# Power_Management.net
KiCad netlist of a schematic drawn in Altium Designer
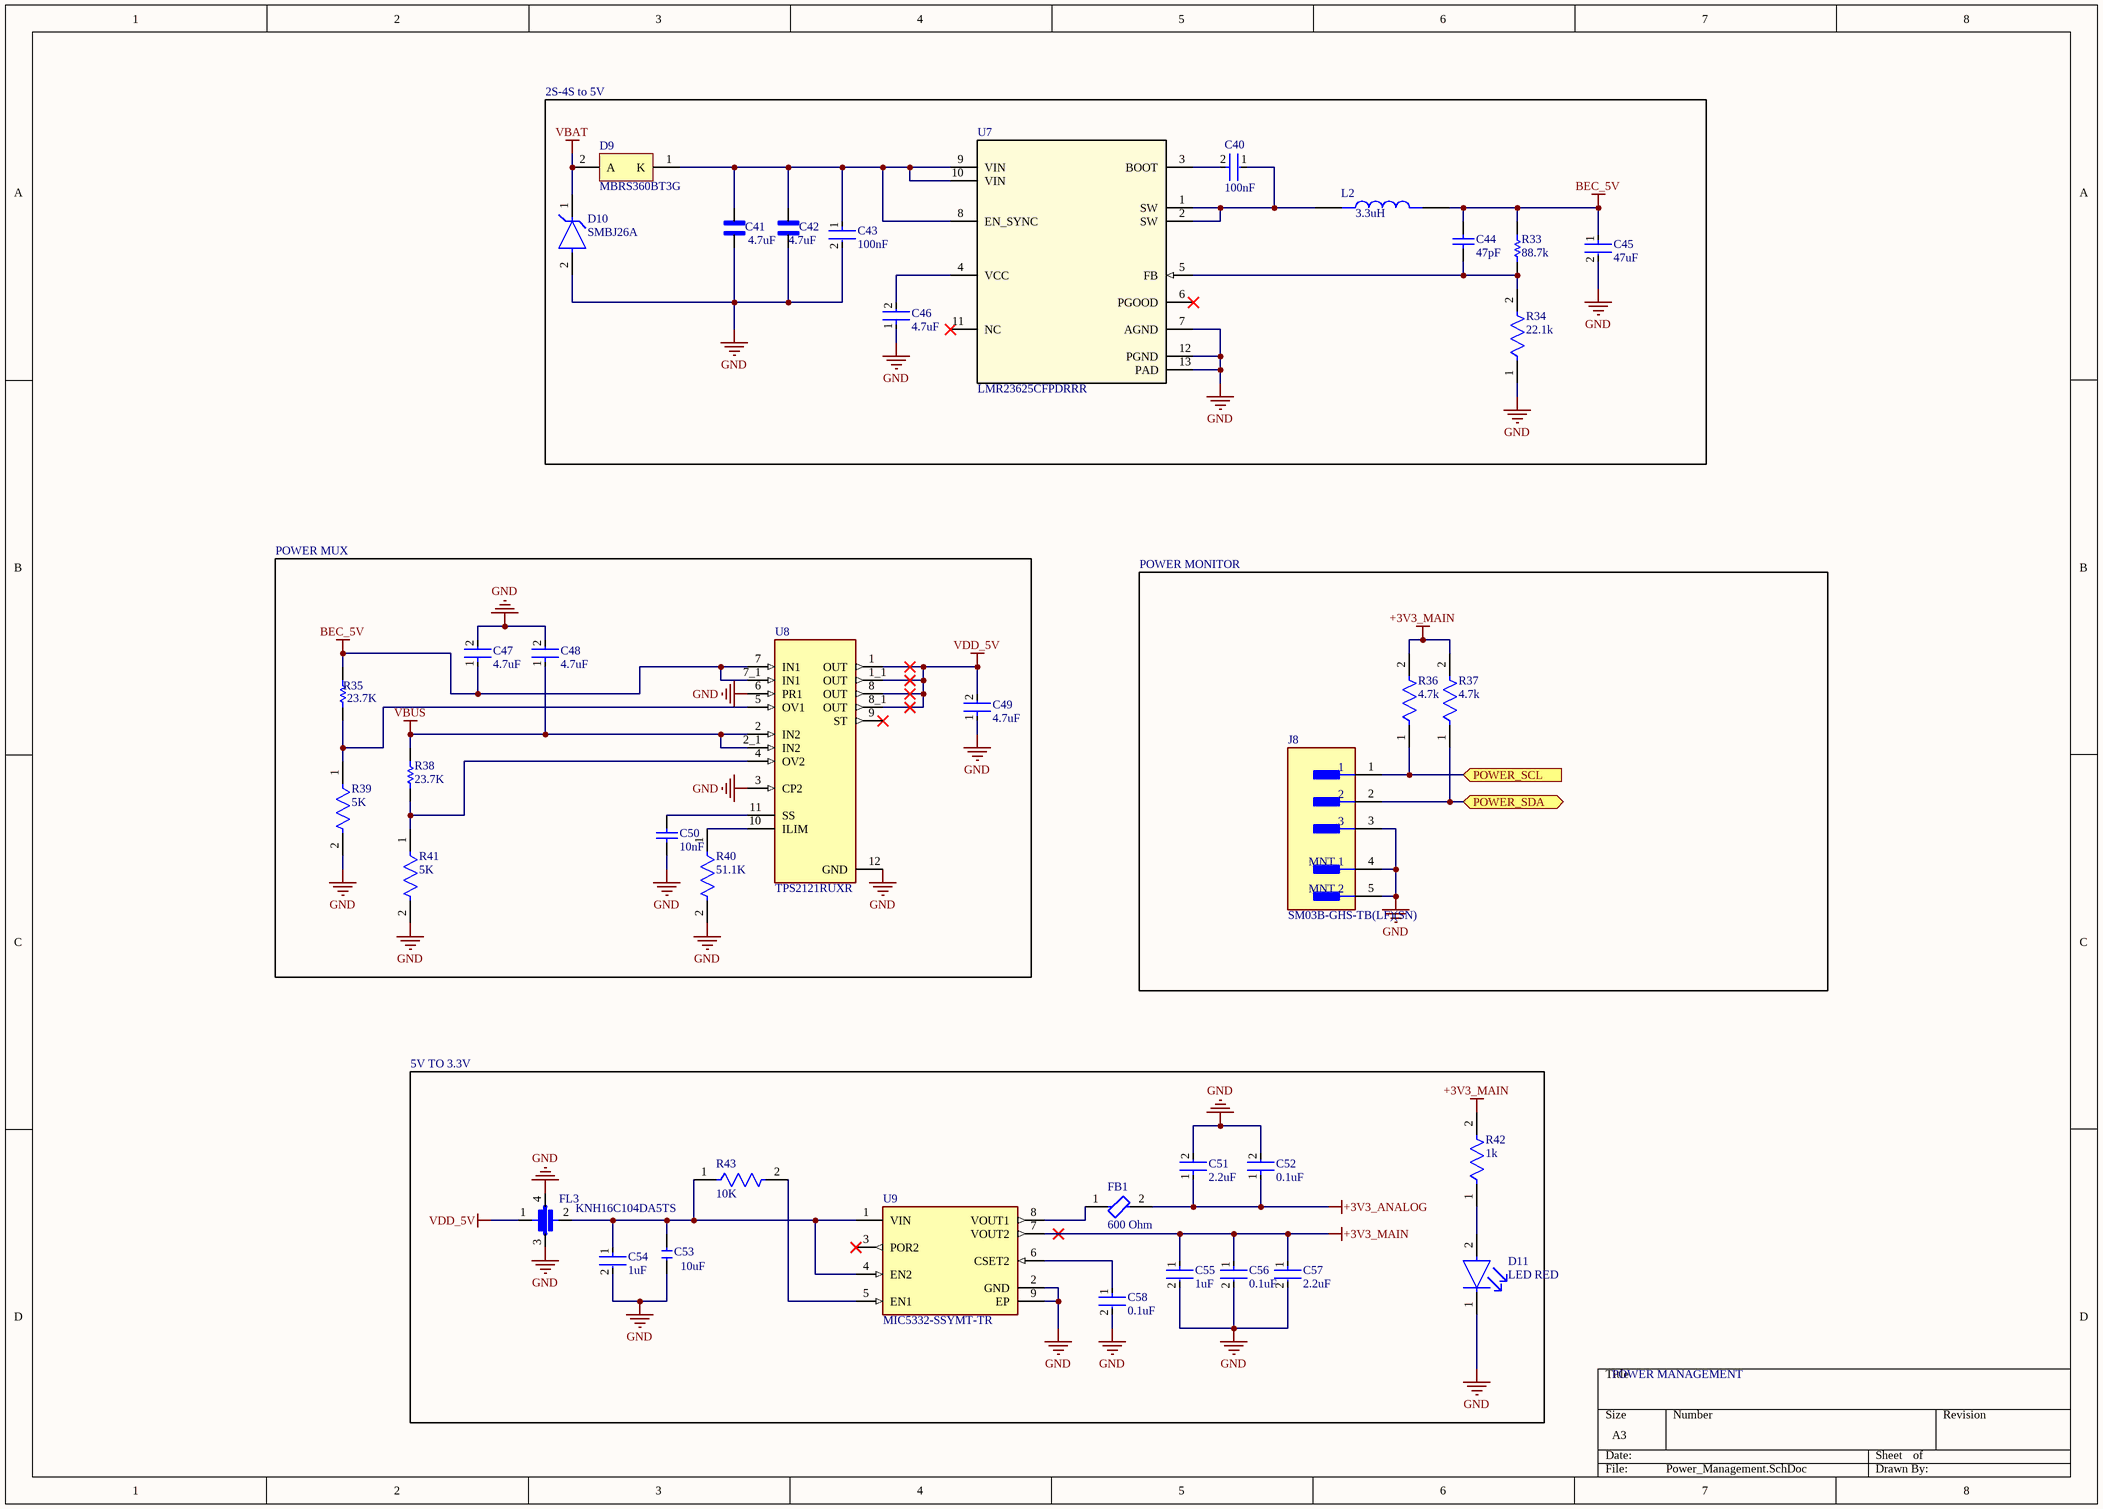
[diagram p0: Power_Management.SchDoc]

(export (version "E")
  (design (tool "Eeschema 10.0.6"))
  (components
    (comp (ref "C40")
      (value "100nF")
      (footprint "FP-GRM15-MFG")
      (description "CAP CER 0.1UF 16V X7R 0402")
      (fields (field (name "MANUFACTURER PART NUMBER") "GRM155R71C104KA88D") (field (name "TOLERANCE") "10%"))
      (libsource (lib "Altium Content Vault") (part "236180d848d6139a670b325ea6854c9"))
    )
    (comp (ref "C41")
      (value "MSASU32MSB7475MPNA01")
      (footprint "CAPC3225X270N")
      (fields (field (name "MF") "{'manufacturer': u'Taiyo Yuden'}"))
      (libsource (lib "4.7uF CAP") (part "MSASU32MSB7475MPNA01"))
    )
    (comp (ref "C42")
      (value "MSASU32MSB7475MPNA01")
      (footprint "CAPC3225X270N")
      (fields (field (name "MF") "{'manufacturer': u'Taiyo Yuden'}"))
      (libsource (lib "4.7uF CAP") (part "MSASU32MSB7475MPNA01"))
    )
    (comp (ref "C43")
      (value "100nF")
      (footprint "FP-CS0402-CA-MFG")
      (description "CS0402KRX7R8BB104 Multilayer Ceramic Capacitor, 0.1 uF, 25 V, ± 10%, X7R, 0402 [1005 Metric]")
      (fields (field (name "TOLERANCE") "10%"))
      (libsource (lib "Altium Content Vault") (part "11868f565c42a9108669ba33697ecf6"))
    )
    (comp (ref "C44")
      (value "47pF")
      (footprint "CAPC1005X55X25NL05T10")
      (fields (field (name "PART NUMBER") "GRM1555C1E470JA01D") (field (name "MANUFACTURER") "Murata"))
      (libsource (lib "Altium Content Vault") (part "CAP"))
    )
    (comp (ref "C45")
      (value "47uF")
      (footprint "FP-GRM31C-0_2-e0_3_0_8-IPC_A")
      (description "Chip Multilayer Ceramic Capacitors for General Purpose, 1206, 47uF, X5R, 15%, 10%, 10V")
      (fields (field (name "TOLERANCE") "10%"))
      (libsource (lib "Altium Content Vault") (part "02cd4be3c70576c341d710602a673aa"))
    )
    (comp (ref "C46")
      (value "4.7uF")
      (footprint "FP-GRT155-0_15-MFG")
      (description "Multi-Layer Ceramic Capacitor 4.7uF 10V X5R ±20% 0402 Paper T/R")
      (libsource (lib "Altium Content Vault") (part "11868f565c42a9108669ba33697ecf6"))
    )
    (comp (ref "C47")
      (value "4.7uF")
      (footprint "FP-GRT155-0_15-MFG")
      (description "Multi-Layer Ceramic Capacitor 4.7uF 10V X5R ±20% 0402 Paper T/R")
      (libsource (lib "Altium Content Vault") (part "11868f565c42a9108669ba33697ecf6"))
    )
    (comp (ref "C48")
      (value "4.7uF")
      (footprint "FP-GRT155-0_15-MFG")
      (description "Multi-Layer Ceramic Capacitor 4.7uF 10V X5R ±20% 0402 Paper T/R")
      (libsource (lib "Altium Content Vault") (part "11868f565c42a9108669ba33697ecf6"))
    )
    (comp (ref "C49")
      (value "4.7uF")
      (footprint "FP-GRT155-0_15-MFG")
      (description "Multi-Layer Ceramic Capacitor 4.7uF 10V X5R ±20% 0402 Paper T/R")
      (libsource (lib "Altium Content Vault") (part "11868f565c42a9108669ba33697ecf6"))
    )
    (comp (ref "C50")
      (value "10nF")
      (footprint "CAPC1005X60X30NL05T10")
      (fields (field (name "PART NUMBER") "C0402C103K3RALTU") (field (name "MANUFACTURER") "Kemet"))
      (libsource (lib "Altium Content Vault") (part "CAP"))
    )
    (comp (ref "C51")
      (value "2.2uF")
      (footprint "FP-GRM155-0_2-IPC_B")
      (description "Chip Multilayer Ceramic Capacitors for General Purpose, 0402, 2.2uF, X7R, 15%, 10%, 10V")
      (libsource (lib "Altium Content Vault") (part "b4654b650e69147ec39a6b967a45e02"))
    )
    (comp (ref "C52")
      (value "0.1uF")
      (footprint "FP-C0402-BB-MFG")
      (description "CAP CER 0.1UF 10V X7R 0402")
      (fields (field (name "MANUFACTURER") "Kemet") (field (name "TOLERANCE") "0.1"))
      (libsource (lib "Altium Content Vault") (part "b4654b650e69147ec39a6b967a45e02"))
    )
    (comp (ref "C53")
      (value "GRM155R60J106ME15D")
      (footprint "C0402")
      (description "10 ÂµF Â±20% 6.3V Ceramic Capacitor X5R 0402 (1005 Metric)")
      (fields (field (name "MF") "Yageo") (field (name "MP") "CC0402MRX5R5BB106"))
      (libsource (lib "CERAMIC-10UF-6.3V-20_-X5R_0402_") (part "CERAMIC-10UF-6.3V-20%-X5R(0402)"))
    )
    (comp (ref "C54")
      (value "1uF")
      (footprint "FP-GRM155-0_1-IPC_A")
      (description "Chip Multilayer Ceramic Capacitors for General Purpose, 0402, 1.0uF, X7R, 15%, 10%, 10V")
      (libsource (lib "Altium Content Vault") (part "11868f565c42a9108669ba33697ecf6"))
    )
    (comp (ref "C55")
      (value "1uF")
      (footprint "FP-GRM155-0_1-IPC_A")
      (description "Chip Multilayer Ceramic Capacitors for General Purpose, 0402, 1.0uF, X7R, 15%, 10%, 10V")
      (libsource (lib "Altium Content Vault") (part "11868f565c42a9108669ba33697ecf6"))
    )
    (comp (ref "C56")
      (value "0.1uF")
      (footprint "FP-C0402-BB-MFG")
      (description "CAP CER 0.1UF 10V X7R 0402")
      (fields (field (name "MANUFACTURER") "Kemet") (field (name "TOLERANCE") "0.1"))
      (libsource (lib "Altium Content Vault") (part "b4654b650e69147ec39a6b967a45e02"))
    )
    (comp (ref "C57")
      (value "2.2uF")
      (footprint "FP-GRM155-0_2-IPC_B")
      (description "Chip Multilayer Ceramic Capacitors for General Purpose, 0402, 2.2uF, X7R, 15%, 10%, 10V")
      (libsource (lib "Altium Content Vault") (part "b4654b650e69147ec39a6b967a45e02"))
    )
    (comp (ref "C58")
      (value "0.1uF")
      (footprint "FP-C0402-BB-MFG")
      (description "CAP CER 0.1UF 10V X7R 0402")
      (fields (field (name "MANUFACTURER") "Kemet") (field (name "TOLERANCE") "0.1"))
      (libsource (lib "Altium Content Vault") (part "b4654b650e69147ec39a6b967a45e02"))
    )
    (comp (ref "D9")
      (value "MBRS360BT3G")
      (footprint "ONSC-SMB-2-403A-03_H_V")
      (description "Schottky Power Rectifier, 2-Pin SMB, Pb-Free, Tape and Reel")
      (fields (field (name "MANUFACTURER") "On Semiconductor"))
      (libsource (lib "Altium Content Vault") (part "ONSC-D-K1A2-2_A"))
    )
    (comp (ref "D10")
      (value "SMBJ26A")
      (footprint "FP-SMBJ-MFG")
      (description "TVS DIODE 26V 42.1V DO214AA")
      (fields
        (field (name "MANUFACTURER") "Littelfuse")
        (field (name "OCTOPART") "https://octopart.com/smbj26a-littelfuse-350771")
      )
      (libsource (lib "Altium Content Vault") (part "f813f71cba58e380607f5dd3caf9714"))
    )
    (comp (ref "D11")
      (value "LED RED")
      (footprint "FP-SML-LXT0805IW-TR-MFG")
      (description "LED RED DIFFUSED SMD")
      (libsource (lib "Altium Content Vault") (part "8706943c75ba83719d021d2fdc84c58"))
    )
    (comp (ref "FB1")
      (value "600 Ohm")
      (footprint "FP-BLM15-0_05-MFG")
      (description "BLM15PE601SH1D Ferrite Bead, 600 Ohm, 25%, 0402 Rohs Compliant: Yes")
      (fields (field (name "TOLERANCE") "25%"))
      (libsource (lib "Altium Content Vault") (part "5f30dd21d616792df468990f7003faa"))
    )
    (comp (ref "FL3")
      (value "KNH16C104DA5TS")
      (footprint "FIL_KNH16C104DA5TS")
      (fields (field (name "MF") "{'manufacturer': u'KYOCERA AVX'}"))
      (libsource (lib "KNH16C104DA5TS") (part "KNH16C104DA5TS"))
    )
    (comp (ref "J8")
      (value "SM03B-GHS-TB(LF)(SN)")
      (footprint "FP-SM03B-GHS-TB_LF_SN-MFG")
      (description "CONN HEADER SMD R/A 3POS 1.25MM")
      (libsource (lib "Altium Content Vault") (part "13850a6865a90496d8e6d51657cef87"))
    )
    (comp (ref "L2")
      (value "IND_XAL4030-332MEB")
      (footprint "IND_XAL4030-332MEB")
      (fields (field (name "MP") "XAL4030-332MEB"))
      (libsource (lib "3.2uH") (part "XAL4030-332MEB"))
    )
    (comp (ref "R33")
      (value "88.7k")
      (footprint "RESC1005X40X25NL05T05")
      (fields (field (name "MANUFACTURER") "Vishay Dale") (field (name "PART NUMBER") "CRCW040288K7FKED"))
      (libsource (lib "Altium Content Vault") (part "RES"))
    )
    (comp (ref "R34")
      (value "22.1k")
      (footprint "FP-CRCW0402-e3-IPC_A")
      (description "RES Thick Film, 22.1kΩ, 1%, 0.063W, 100ppm/°C, 0402")
      (fields (field (name "TOLERANCE") "1%"))
      (libsource (lib "Altium Content Vault") (part "1029c3af85768c4190bb7ad29bc67b5"))
    )
    (comp (ref "R35")
      (value "23.7K")
      (footprint "RESC1005X40X25LL05T05")
      (fields (field (name "MANUFACTURER") "Vishay Dale") (field (name "PART NUMBER") "CRCW040223K7FKTD"))
      (libsource (lib "Altium Content Vault") (part "RES"))
    )
    (comp (ref "R36")
      (value "4.7k")
      (footprint "FP-TFCR0402-IPC_A")
      (description "RES Thin Film,  4.7kΩ, 0.5%, 0.063W, 25ppm/°C, 0402")
      (libsource (lib "Altium Content Vault") (part "1029c3af85768c4190bb7ad29bc67b5"))
    )
    (comp (ref "R37")
      (value "4.7k")
      (footprint "FP-TFCR0402-IPC_A")
      (description "RES Thin Film,  4.7kΩ, 0.5%, 0.063W, 25ppm/°C, 0402")
      (libsource (lib "Altium Content Vault") (part "1029c3af85768c4190bb7ad29bc67b5"))
    )
    (comp (ref "R38")
      (value "23.7K")
      (footprint "RESC1005X40X25LL05T05")
      (fields (field (name "MANUFACTURER") "Vishay Dale") (field (name "PART NUMBER") "CRCW040223K7FKTD"))
      (libsource (lib "Altium Content Vault") (part "RES"))
    )
    (comp (ref "R39")
      (value "5K")
      (footprint "FP-PNM0402-IPC_C")
      (description "RES SMD 5K OHM 0.1% 1/20W 0402")
      (fields (field (name "TOLERANCE") "0.1%"))
      (libsource (lib "Altium Content Vault") (part "1029c3af85768c4190bb7ad29bc67b5"))
    )
    (comp (ref "R40")
      (value "51.1K")
      (footprint "FP-RK73H1E-IPC_C")
      (description "51.1kΩ ±1% 0.1W Chip Resistor 0402 Thick Film AEC-Q200 Qualified")
      (fields (field (name "TOLERANCE") "1%"))
      (libsource (lib "Altium Content Vault") (part "1029c3af85768c4190bb7ad29bc67b5"))
    )
    (comp (ref "R41")
      (value "5K")
      (footprint "FP-PNM0402-IPC_C")
      (description "RES SMD 5K OHM 0.1% 1/20W 0402")
      (fields (field (name "TOLERANCE") "0.1%"))
      (libsource (lib "Altium Content Vault") (part "1029c3af85768c4190bb7ad29bc67b5"))
    )
    (comp (ref "R42")
      (value "1k")
      (footprint "FP-MCS0402-IPC_A")
      (description "RES SMD 1.2K OHM 1% 1/10W 0402")
      (fields (field (name "TOLERANCE") "0.5%"))
      (libsource (lib "Altium Content Vault") (part "1029c3af85768c4190bb7ad29bc67b5"))
    )
    (comp (ref "R43")
      (value "10K")
      (footprint "FP-MCS0402-MFG")
      (description "RES SMD 1.2K OHM 1% 1/10W 0402")
      (fields (field (name "TOLERANCE") "0.5%"))
      (libsource (lib "Altium Content Vault") (part "1029c3af85768c4190bb7ad29bc67b5"))
    )
    (comp (ref "U7")
      (value "LMR23625CFPDRRR")
      (footprint "DRR0012D")
      (description "SIMPLE SWITCHERÂ®, 36V 2.5A Synchronous Step-Down Converter 12-WSON -40 to 125")
      (fields (field (name "COPYRIGHT") "Copyright (C) 2025 Ultra Librarian. All rights reserved."))
      (libsource (lib "LMR23625CFPDRRR") (part "LMR23625CFPDRRR"))
    )
    (comp (ref "U8")
      (value "TPS2121RUXR")
      (footprint "IC_TPS2121RUXR")
      (description "2.7-V&nbsp;to 22-V, 56-mâ„¦, 4.5-A, power mux with seamless switchover")
      (fields (field (name "MF") "Texas Instruments"))
      (libsource (lib "TPS2121RUXR") (part "TPS2121RUXR"))
    )
    (comp (ref "U9")
      (value "MIC5332-SSYMT-TR")
      (footprint "FP-MIC5332-SSYMT-TR-IPC_C")
      (description "IC REG LINEAR 3.3V/3.3V 8TMLF")
      (libsource (lib "Altium Content Vault") (part "3cda86a0174568058fc5e6010d9da67"))
    )
  )
  (nets
    (net (code "1") (name "+3V3_ANALOG") (class "Default")
      (node (ref "C51") (pin "1") (pinfunction "1_1") (pintype "passive"))
      (node (ref "C52") (pin "1") (pinfunction "1_1") (pintype "passive"))
      (node (ref "FB1") (pin "2") (pinfunction "2_2") (pintype "passive"))
    )
    (net (code "2") (name "+3V3_MAIN") (class "Default")
      (node (ref "C55") (pin "1") (pinfunction "1_1") (pintype "passive"))
      (node (ref "C56") (pin "1") (pinfunction "1_1") (pintype "passive"))
      (node (ref "C57") (pin "1") (pinfunction "1_1") (pintype "passive"))
      (node (ref "R36") (pin "2") (pinfunction "2_2") (pintype "passive"))
      (node (ref "R37") (pin "2") (pinfunction "2_2") (pintype "passive"))
      (node (ref "R42") (pin "2") (pinfunction "2_2") (pintype "passive"))
      (node (ref "U9") (pin "7") (pinfunction "VOUT2_7") (pintype "output"))
    )
    (net (code "3") (name "/POWER_SCL") (class "Default")
      (node (ref "J8") (pin "1") (pinfunction "1_1") (pintype "passive"))
      (node (ref "R36") (pin "1") (pinfunction "1_1") (pintype "passive"))
    )
    (net (code "4") (name "/POWER_SDA") (class "Default")
      (node (ref "J8") (pin "2") (pinfunction "2_2") (pintype "passive"))
      (node (ref "R37") (pin "1") (pinfunction "1_1") (pintype "passive"))
    )
    (net (code "5") (name "BEC_5V") (class "Default")
      (node (ref "C44") (pin "2") (pinfunction "2_2") (pintype "passive"))
      (node (ref "C45") (pin "1") (pinfunction "1_1") (pintype "passive"))
      (node (ref "C47") (pin "1") (pinfunction "1_1") (pintype "passive"))
      (node (ref "L2") (pin "2") (pinfunction "2_2") (pintype "passive"))
      (node (ref "R33") (pin "2") (pinfunction "2_2") (pintype "passive"))
      (node (ref "R35") (pin "2") (pinfunction "2_2") (pintype "passive"))
      (node (ref "U8") (pin "7") (pinfunction "IN1_7") (pintype "input"))
      (node (ref "U8") (pin "7_1") (pinfunction "IN1_7_1") (pintype "input"))
    )
    (net (code "6") (name "GND") (class "Default")
      (node (ref "C41") (pin "1") (pinfunction "1_1") (pintype "passive"))
      (node (ref "C42") (pin "1") (pinfunction "1_1") (pintype "passive"))
      (node (ref "C43") (pin "2") (pinfunction "2_2") (pintype "passive"))
      (node (ref "C45") (pin "2") (pinfunction "2_2") (pintype "passive"))
      (node (ref "C46") (pin "1") (pinfunction "1_1") (pintype "passive"))
      (node (ref "C47") (pin "2") (pinfunction "2_2") (pintype "passive"))
      (node (ref "C48") (pin "2") (pinfunction "2_2") (pintype "passive"))
      (node (ref "C49") (pin "1") (pinfunction "1_1") (pintype "passive"))
      (node (ref "C50") (pin "1") (pinfunction "1_1") (pintype "passive"))
      (node (ref "C51") (pin "2") (pinfunction "2_2") (pintype "passive"))
      (node (ref "C52") (pin "2") (pinfunction "2_2") (pintype "passive"))
      (node (ref "C53") (pin "1") (pinfunction "1_1") (pintype "passive"))
      (node (ref "C54") (pin "2") (pinfunction "2_2") (pintype "passive"))
      (node (ref "C55") (pin "2") (pinfunction "2_2") (pintype "passive"))
      (node (ref "C56") (pin "2") (pinfunction "2_2") (pintype "passive"))
      (node (ref "C57") (pin "2") (pinfunction "2_2") (pintype "passive"))
      (node (ref "C58") (pin "2") (pinfunction "2_2") (pintype "passive"))
      (node (ref "D10") (pin "2") (pinfunction "A_2") (pintype "passive"))
      (node (ref "D11") (pin "1") (pinfunction "C_1") (pintype "passive"))
      (node (ref "FL3") (pin "3") (pinfunction "3_3") (pintype "passive"))
      (node (ref "FL3") (pin "4") (pinfunction "4_4") (pintype "passive"))
      (node (ref "J8") (pin "3") (pinfunction "3_3") (pintype "passive"))
      (node (ref "J8") (pin "4") (pinfunction "MNT_1_4") (pintype "passive"))
      (node (ref "J8") (pin "5") (pinfunction "MNT_2_5") (pintype "passive"))
      (node (ref "R34") (pin "1") (pinfunction "1_1") (pintype "passive"))
      (node (ref "R39") (pin "2") (pinfunction "2_2") (pintype "passive"))
      (node (ref "R40") (pin "2") (pinfunction "2_2") (pintype "passive"))
      (node (ref "R41") (pin "2") (pinfunction "2_2") (pintype "passive"))
      (node (ref "U7") (pin "12") (pinfunction "PGND_12") (pintype "power_in"))
      (node (ref "U7") (pin "13") (pinfunction "PAD_13") (pintype "power_in"))
      (node (ref "U7") (pin "7") (pinfunction "AGND_7") (pintype "power_in"))
      (node (ref "U8") (pin "12") (pinfunction "GND_12") (pintype "power_in"))
      (node (ref "U8") (pin "3") (pinfunction "CP2_3") (pintype "input"))
      (node (ref "U8") (pin "6") (pinfunction "PR1_6") (pintype "input"))
      (node (ref "U9") (pin "2") (pinfunction "GND_2") (pintype "power_in"))
      (node (ref "U9") (pin "9") (pinfunction "EP_9") (pintype "power_in"))
    )
    (net (code "7") (name "Net-(C40-Pad1)") (class "Default")
      (node (ref "C40") (pin "1") (pinfunction "1_1") (pintype "passive"))
      (node (ref "L2") (pin "1") (pinfunction "1_1") (pintype "passive"))
      (node (ref "U7") (pin "1") (pinfunction "SW_1") (pintype "power_in"))
      (node (ref "U7") (pin "2") (pinfunction "SW_2") (pintype "power_in"))
    )
    (net (code "8") (name "Net-(D9-K)") (class "Default")
      (node (ref "C41") (pin "2") (pinfunction "2_2") (pintype "passive"))
      (node (ref "C42") (pin "2") (pinfunction "2_2") (pintype "passive"))
      (node (ref "C43") (pin "1") (pinfunction "1_1") (pintype "passive"))
      (node (ref "D9") (pin "1") (pinfunction "K_1") (pintype "passive"))
      (node (ref "U7") (pin "10") (pinfunction "VIN_10") (pintype "power_in"))
      (node (ref "U7") (pin "8") (pinfunction "EN_SYNC_8") (pintype "power_in"))
      (node (ref "U7") (pin "9") (pinfunction "VIN_9") (pintype "power_in"))
    )
    (net (code "9") (name "Net-(D11-A)") (class "Default")
      (node (ref "D11") (pin "2") (pinfunction "A_2") (pintype "passive"))
      (node (ref "R42") (pin "1") (pinfunction "1_1") (pintype "passive"))
    )
    (net (code "10") (name "Net-(U7-BOOT)") (class "Default")
      (node (ref "C40") (pin "2") (pinfunction "2_2") (pintype "passive"))
      (node (ref "U7") (pin "3") (pinfunction "BOOT_3") (pintype "power_in"))
    )
    (net (code "11") (name "Net-(U7-FB)") (class "Default")
      (node (ref "C44") (pin "1") (pinfunction "1_1") (pintype "passive"))
      (node (ref "R33") (pin "1") (pinfunction "1_1") (pintype "passive"))
      (node (ref "R34") (pin "2") (pinfunction "2_2") (pintype "passive"))
      (node (ref "U7") (pin "5") (pinfunction "FB_5") (pintype "input"))
    )
    (net (code "12") (name "Net-(U7-VCC)") (class "Default")
      (node (ref "C46") (pin "2") (pinfunction "2_2") (pintype "passive"))
      (node (ref "U7") (pin "4") (pinfunction "VCC_4") (pintype "power_in"))
    )
    (net (code "13") (name "Net-(U8-ILIM)") (class "Default")
      (node (ref "R40") (pin "1") (pinfunction "1_1") (pintype "passive"))
      (node (ref "U8") (pin "10") (pinfunction "ILIM_10") (pintype "passive"))
    )
    (net (code "14") (name "Net-(U8-OV1)") (class "Default")
      (node (ref "R35") (pin "1") (pinfunction "1_1") (pintype "passive"))
      (node (ref "R39") (pin "1") (pinfunction "1_1") (pintype "passive"))
      (node (ref "U8") (pin "5") (pinfunction "OV1_5") (pintype "input"))
    )
    (net (code "15") (name "Net-(U8-OV2)") (class "Default")
      (node (ref "R38") (pin "1") (pinfunction "1_1") (pintype "passive"))
      (node (ref "R41") (pin "1") (pinfunction "1_1") (pintype "passive"))
      (node (ref "U8") (pin "4") (pinfunction "OV2_4") (pintype "input"))
    )
    (net (code "16") (name "Net-(U8-SS)") (class "Default")
      (node (ref "C50") (pin "2") (pinfunction "2_2") (pintype "passive"))
      (node (ref "U8") (pin "11") (pinfunction "SS_11") (pintype "passive"))
    )
    (net (code "17") (name "Net-(U9-CSET2)") (class "Default")
      (node (ref "C58") (pin "1") (pinfunction "1_1") (pintype "passive"))
      (node (ref "U9") (pin "6") (pinfunction "CSET2_6") (pintype "input"))
    )
    (net (code "18") (name "Net-(U9-EN1)") (class "Default")
      (node (ref "R43") (pin "2") (pinfunction "2_2") (pintype "passive"))
      (node (ref "U9") (pin "5") (pinfunction "EN1_5") (pintype "input"))
    )
    (net (code "19") (name "Net-(U9-EN2)") (class "Default")
      (node (ref "C53") (pin "2") (pinfunction "2_2") (pintype "passive"))
      (node (ref "C54") (pin "1") (pinfunction "1_1") (pintype "passive"))
      (node (ref "FL3") (pin "2") (pinfunction "2_2") (pintype "passive"))
      (node (ref "R43") (pin "1") (pinfunction "1_1") (pintype "passive"))
      (node (ref "U9") (pin "1") (pinfunction "VIN_1") (pintype "power_in"))
      (node (ref "U9") (pin "4") (pinfunction "EN2_4") (pintype "input"))
    )
    (net (code "20") (name "Net-(U9-VOUT1)") (class "Default")
      (node (ref "FB1") (pin "1") (pinfunction "1_1") (pintype "passive"))
      (node (ref "U9") (pin "8") (pinfunction "VOUT1_8") (pintype "output"))
    )
    (net (code "21") (name "VBAT") (class "Default")
      (node (ref "D10") (pin "1") (pinfunction "C_1") (pintype "passive"))
      (node (ref "D9") (pin "2") (pinfunction "A_2") (pintype "passive"))
    )
    (net (code "22") (name "VBUS") (class "Default")
      (node (ref "C48") (pin "1") (pinfunction "1_1") (pintype "passive"))
      (node (ref "R38") (pin "2") (pinfunction "2_2") (pintype "passive"))
      (node (ref "U8") (pin "2") (pinfunction "IN2_2") (pintype "input"))
      (node (ref "U8") (pin "2_1") (pinfunction "IN2_2_1") (pintype "input"))
    )
    (net (code "23") (name "VDD_5V") (class "Default")
      (node (ref "C49") (pin "2") (pinfunction "2_2") (pintype "passive"))
      (node (ref "FL3") (pin "1") (pinfunction "1_1") (pintype "passive"))
      (node (ref "U8") (pin "1") (pinfunction "OUT_1") (pintype "output"))
      (node (ref "U8") (pin "1_1") (pinfunction "OUT_1_1") (pintype "output"))
      (node (ref "U8") (pin "8") (pinfunction "OUT_8") (pintype "output"))
      (node (ref "U8") (pin "8_1") (pinfunction "OUT_8_1") (pintype "output"))
    )
    (net (code "24") (name "unconnected-(U7-NC-Pad11)") (class "Default")
      (node (ref "U7") (pin "11") (pinfunction "NC_11") (pintype "power_in+no_connect"))
    )
    (net (code "25") (name "unconnected-(U7-PGOOD-Pad6)") (class "Default")
      (node (ref "U7") (pin "6") (pinfunction "PGOOD_6") (pintype "passive+no_connect"))
    )
    (net (code "26") (name "unconnected-(U8-ST-Pad9)") (class "Default")
      (node (ref "U8") (pin "9") (pinfunction "ST_9") (pintype "output+no_connect"))
    )
    (net (code "27") (name "unconnected-(U9-POR2-Pad3)") (class "Default")
      (node (ref "U9") (pin "3") (pinfunction "POR2_3") (pintype "output+no_connect"))
    )
  )
)
